# Key_Matrix.net
KiCad netlist of a schematic drawn in Altium Designer
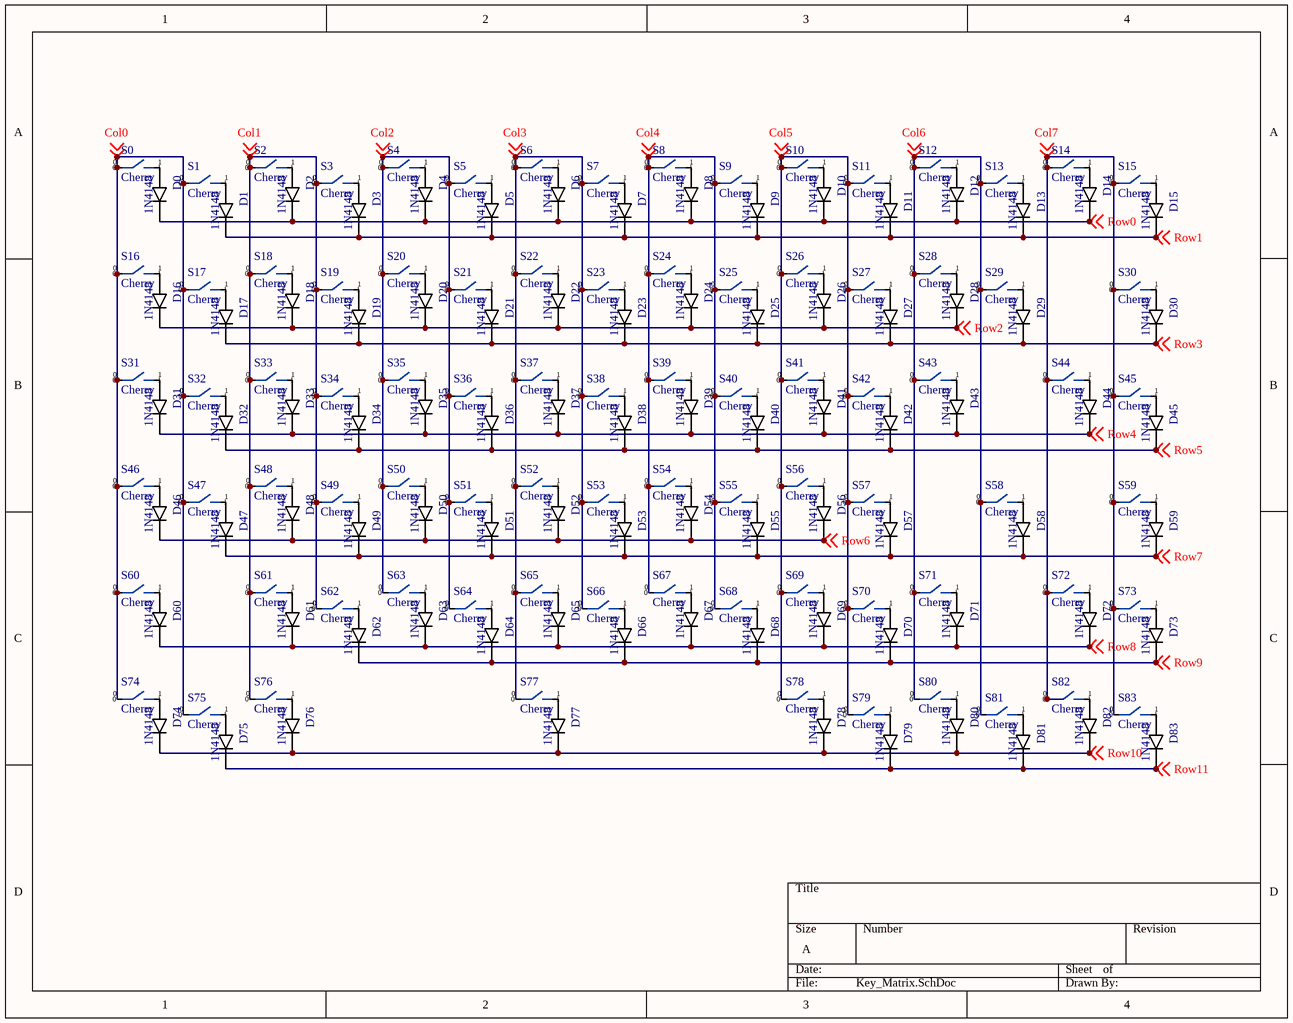
[diagram p0: Key_Matrix.SchDoc]

(export (version "E")
  (design (tool "Eeschema 10.0.6"))
  (components
    (comp (ref "D0")
      (value "1N4148")
      (footprint "DIOAD829W49L456D191_1N4148(Primary)")
      (description "Diode Small Signal Switching 100V 0.3A 2-Pin DO-35")
      (fields (field (name "MF") "MICROSS/On Semiconductor"))
      (libsource (lib "1N4148") (part "1N4148"))
    )
    (comp (ref "D1")
      (value "1N4148")
      (footprint "DIOAD829W49L456D191_1N4148(Primary)")
      (description "Diode Small Signal Switching 100V 0.3A 2-Pin DO-35")
      (fields (field (name "MF") "MICROSS/On Semiconductor"))
      (libsource (lib "1N4148") (part "1N4148"))
    )
    (comp (ref "D2")
      (value "1N4148")
      (footprint "DIOAD829W49L456D191_1N4148(Primary)")
      (description "Diode Small Signal Switching 100V 0.3A 2-Pin DO-35")
      (fields (field (name "MF") "MICROSS/On Semiconductor"))
      (libsource (lib "1N4148") (part "1N4148"))
    )
    (comp (ref "D3")
      (value "1N4148")
      (footprint "DIOAD829W49L456D191_1N4148(Primary)")
      (description "Diode Small Signal Switching 100V 0.3A 2-Pin DO-35")
      (fields (field (name "MF") "MICROSS/On Semiconductor"))
      (libsource (lib "1N4148") (part "1N4148"))
    )
    (comp (ref "D4")
      (value "1N4148")
      (footprint "DIOAD829W49L456D191_1N4148(Primary)")
      (description "Diode Small Signal Switching 100V 0.3A 2-Pin DO-35")
      (fields (field (name "MF") "MICROSS/On Semiconductor"))
      (libsource (lib "1N4148") (part "1N4148"))
    )
    (comp (ref "D5")
      (value "1N4148")
      (footprint "DIOAD829W49L456D191_1N4148(Primary)")
      (description "Diode Small Signal Switching 100V 0.3A 2-Pin DO-35")
      (fields (field (name "MF") "MICROSS/On Semiconductor"))
      (libsource (lib "1N4148") (part "1N4148"))
    )
    (comp (ref "D6")
      (value "1N4148")
      (footprint "DIOAD829W49L456D191_1N4148(Primary)")
      (description "Diode Small Signal Switching 100V 0.3A 2-Pin DO-35")
      (fields (field (name "MF") "MICROSS/On Semiconductor"))
      (libsource (lib "1N4148") (part "1N4148"))
    )
    (comp (ref "D7")
      (value "1N4148")
      (footprint "DIOAD829W49L456D191_1N4148(Primary)")
      (description "Diode Small Signal Switching 100V 0.3A 2-Pin DO-35")
      (fields (field (name "MF") "MICROSS/On Semiconductor"))
      (libsource (lib "1N4148") (part "1N4148"))
    )
    (comp (ref "D8")
      (value "1N4148")
      (footprint "DIOAD829W49L456D191_1N4148(Primary)")
      (description "Diode Small Signal Switching 100V 0.3A 2-Pin DO-35")
      (fields (field (name "MF") "MICROSS/On Semiconductor"))
      (libsource (lib "1N4148") (part "1N4148"))
    )
    (comp (ref "D9")
      (value "1N4148")
      (footprint "DIOAD829W49L456D191_1N4148(Primary)")
      (description "Diode Small Signal Switching 100V 0.3A 2-Pin DO-35")
      (fields (field (name "MF") "MICROSS/On Semiconductor"))
      (libsource (lib "1N4148") (part "1N4148"))
    )
    (comp (ref "D10")
      (value "1N4148")
      (footprint "DIOAD829W49L456D191_1N4148(Primary)")
      (description "Diode Small Signal Switching 100V 0.3A 2-Pin DO-35")
      (fields (field (name "MF") "MICROSS/On Semiconductor"))
      (libsource (lib "1N4148") (part "1N4148"))
    )
    (comp (ref "D11")
      (value "1N4148")
      (footprint "DIOAD829W49L456D191_1N4148(Primary)")
      (description "Diode Small Signal Switching 100V 0.3A 2-Pin DO-35")
      (fields (field (name "MF") "MICROSS/On Semiconductor"))
      (libsource (lib "1N4148") (part "1N4148"))
    )
    (comp (ref "D12")
      (value "1N4148")
      (footprint "DIOAD829W49L456D191_1N4148(Primary)")
      (description "Diode Small Signal Switching 100V 0.3A 2-Pin DO-35")
      (fields (field (name "MF") "MICROSS/On Semiconductor"))
      (libsource (lib "1N4148") (part "1N4148"))
    )
    (comp (ref "D13")
      (value "1N4148")
      (footprint "DIOAD829W49L456D191_1N4148(Primary)")
      (description "Diode Small Signal Switching 100V 0.3A 2-Pin DO-35")
      (fields (field (name "MF") "MICROSS/On Semiconductor"))
      (libsource (lib "1N4148") (part "1N4148"))
    )
    (comp (ref "D14")
      (value "1N4148")
      (footprint "DIOAD829W49L456D191_1N4148(Primary)")
      (description "Diode Small Signal Switching 100V 0.3A 2-Pin DO-35")
      (fields (field (name "MF") "MICROSS/On Semiconductor"))
      (libsource (lib "1N4148") (part "1N4148"))
    )
    (comp (ref "D15")
      (value "1N4148")
      (footprint "DIOAD829W49L456D191_1N4148(Primary)")
      (description "Diode Small Signal Switching 100V 0.3A 2-Pin DO-35")
      (fields (field (name "MF") "MICROSS/On Semiconductor"))
      (libsource (lib "1N4148") (part "1N4148"))
    )
    (comp (ref "D16")
      (value "1N4148")
      (footprint "DIOAD829W49L456D191_1N4148(Primary)")
      (description "Diode Small Signal Switching 100V 0.3A 2-Pin DO-35")
      (fields (field (name "MF") "MICROSS/On Semiconductor"))
      (libsource (lib "1N4148") (part "1N4148"))
    )
    (comp (ref "D17")
      (value "1N4148")
      (footprint "DIOAD829W49L456D191_1N4148(Primary)")
      (description "Diode Small Signal Switching 100V 0.3A 2-Pin DO-35")
      (fields (field (name "MF") "MICROSS/On Semiconductor"))
      (libsource (lib "1N4148") (part "1N4148"))
    )
    (comp (ref "D18")
      (value "1N4148")
      (footprint "DIOAD829W49L456D191_1N4148(Primary)")
      (description "Diode Small Signal Switching 100V 0.3A 2-Pin DO-35")
      (fields (field (name "MF") "MICROSS/On Semiconductor"))
      (libsource (lib "1N4148") (part "1N4148"))
    )
    (comp (ref "D19")
      (value "1N4148")
      (footprint "DIOAD829W49L456D191_1N4148(Primary)")
      (description "Diode Small Signal Switching 100V 0.3A 2-Pin DO-35")
      (fields (field (name "MF") "MICROSS/On Semiconductor"))
      (libsource (lib "1N4148") (part "1N4148"))
    )
    (comp (ref "D20")
      (value "1N4148")
      (footprint "DIOAD829W49L456D191_1N4148(Primary)")
      (description "Diode Small Signal Switching 100V 0.3A 2-Pin DO-35")
      (fields (field (name "MF") "MICROSS/On Semiconductor"))
      (libsource (lib "1N4148") (part "1N4148"))
    )
    (comp (ref "D21")
      (value "1N4148")
      (footprint "DIOAD829W49L456D191_1N4148(Primary)")
      (description "Diode Small Signal Switching 100V 0.3A 2-Pin DO-35")
      (fields (field (name "MF") "MICROSS/On Semiconductor"))
      (libsource (lib "1N4148") (part "1N4148"))
    )
    (comp (ref "D22")
      (value "1N4148")
      (footprint "DIOAD829W49L456D191_1N4148(Primary)")
      (description "Diode Small Signal Switching 100V 0.3A 2-Pin DO-35")
      (fields (field (name "MF") "MICROSS/On Semiconductor"))
      (libsource (lib "1N4148") (part "1N4148"))
    )
    (comp (ref "D23")
      (value "1N4148")
      (footprint "DIOAD829W49L456D191_1N4148(Primary)")
      (description "Diode Small Signal Switching 100V 0.3A 2-Pin DO-35")
      (fields (field (name "MF") "MICROSS/On Semiconductor"))
      (libsource (lib "1N4148") (part "1N4148"))
    )
    (comp (ref "D24")
      (value "1N4148")
      (footprint "DIOAD829W49L456D191_1N4148(Primary)")
      (description "Diode Small Signal Switching 100V 0.3A 2-Pin DO-35")
      (fields (field (name "MF") "MICROSS/On Semiconductor"))
      (libsource (lib "1N4148") (part "1N4148"))
    )
    (comp (ref "D25")
      (value "1N4148")
      (footprint "DIOAD829W49L456D191_1N4148(Primary)")
      (description "Diode Small Signal Switching 100V 0.3A 2-Pin DO-35")
      (fields (field (name "MF") "MICROSS/On Semiconductor"))
      (libsource (lib "1N4148") (part "1N4148"))
    )
    (comp (ref "D26")
      (value "1N4148")
      (footprint "DIOAD829W49L456D191_1N4148(Primary)")
      (description "Diode Small Signal Switching 100V 0.3A 2-Pin DO-35")
      (fields (field (name "MF") "MICROSS/On Semiconductor"))
      (libsource (lib "1N4148") (part "1N4148"))
    )
    (comp (ref "D27")
      (value "1N4148")
      (footprint "DIOAD829W49L456D191_1N4148(Primary)")
      (description "Diode Small Signal Switching 100V 0.3A 2-Pin DO-35")
      (fields (field (name "MF") "MICROSS/On Semiconductor"))
      (libsource (lib "1N4148") (part "1N4148"))
    )
    (comp (ref "D28")
      (value "1N4148")
      (footprint "DIOAD829W49L456D191_1N4148(Primary)")
      (description "Diode Small Signal Switching 100V 0.3A 2-Pin DO-35")
      (fields (field (name "MF") "MICROSS/On Semiconductor"))
      (libsource (lib "1N4148") (part "1N4148"))
    )
    (comp (ref "D29")
      (value "1N4148")
      (footprint "DIOAD829W49L456D191_1N4148(Primary)")
      (description "Diode Small Signal Switching 100V 0.3A 2-Pin DO-35")
      (fields (field (name "MF") "MICROSS/On Semiconductor"))
      (libsource (lib "1N4148") (part "1N4148"))
    )
    (comp (ref "D30")
      (value "1N4148")
      (footprint "DIOAD829W49L456D191_1N4148(Primary)")
      (description "Diode Small Signal Switching 100V 0.3A 2-Pin DO-35")
      (fields (field (name "MF") "MICROSS/On Semiconductor"))
      (libsource (lib "1N4148") (part "1N4148"))
    )
    (comp (ref "D31")
      (value "1N4148")
      (footprint "DIOAD829W49L456D191_1N4148(Primary)")
      (description "Diode Small Signal Switching 100V 0.3A 2-Pin DO-35")
      (fields (field (name "MF") "MICROSS/On Semiconductor"))
      (libsource (lib "1N4148") (part "1N4148"))
    )
    (comp (ref "D32")
      (value "1N4148")
      (footprint "DIOAD829W49L456D191_1N4148(Primary)")
      (description "Diode Small Signal Switching 100V 0.3A 2-Pin DO-35")
      (fields (field (name "MF") "MICROSS/On Semiconductor"))
      (libsource (lib "1N4148") (part "1N4148"))
    )
    (comp (ref "D33")
      (value "1N4148")
      (footprint "DIOAD829W49L456D191_1N4148(Primary)")
      (description "Diode Small Signal Switching 100V 0.3A 2-Pin DO-35")
      (fields (field (name "MF") "MICROSS/On Semiconductor"))
      (libsource (lib "1N4148") (part "1N4148"))
    )
    (comp (ref "D34")
      (value "1N4148")
      (footprint "DIOAD829W49L456D191_1N4148(Primary)")
      (description "Diode Small Signal Switching 100V 0.3A 2-Pin DO-35")
      (fields (field (name "MF") "MICROSS/On Semiconductor"))
      (libsource (lib "1N4148") (part "1N4148"))
    )
    (comp (ref "D35")
      (value "1N4148")
      (footprint "DIOAD829W49L456D191_1N4148(Primary)")
      (description "Diode Small Signal Switching 100V 0.3A 2-Pin DO-35")
      (fields (field (name "MF") "MICROSS/On Semiconductor"))
      (libsource (lib "1N4148") (part "1N4148"))
    )
    (comp (ref "D36")
      (value "1N4148")
      (footprint "DIOAD829W49L456D191_1N4148(Primary)")
      (description "Diode Small Signal Switching 100V 0.3A 2-Pin DO-35")
      (fields (field (name "MF") "MICROSS/On Semiconductor"))
      (libsource (lib "1N4148") (part "1N4148"))
    )
    (comp (ref "D37")
      (value "1N4148")
      (footprint "DIOAD829W49L456D191_1N4148(Primary)")
      (description "Diode Small Signal Switching 100V 0.3A 2-Pin DO-35")
      (fields (field (name "MF") "MICROSS/On Semiconductor"))
      (libsource (lib "1N4148") (part "1N4148"))
    )
    (comp (ref "D38")
      (value "1N4148")
      (footprint "DIOAD829W49L456D191_1N4148(Primary)")
      (description "Diode Small Signal Switching 100V 0.3A 2-Pin DO-35")
      (fields (field (name "MF") "MICROSS/On Semiconductor"))
      (libsource (lib "1N4148") (part "1N4148"))
    )
    (comp (ref "D39")
      (value "1N4148")
      (footprint "DIOAD829W49L456D191_1N4148(Primary)")
      (description "Diode Small Signal Switching 100V 0.3A 2-Pin DO-35")
      (fields (field (name "MF") "MICROSS/On Semiconductor"))
      (libsource (lib "1N4148") (part "1N4148"))
    )
    (comp (ref "D40")
      (value "1N4148")
      (footprint "DIOAD829W49L456D191_1N4148(Primary)")
      (description "Diode Small Signal Switching 100V 0.3A 2-Pin DO-35")
      (fields (field (name "MF") "MICROSS/On Semiconductor"))
      (libsource (lib "1N4148") (part "1N4148"))
    )
    (comp (ref "D41")
      (value "1N4148")
      (footprint "DIOAD829W49L456D191_1N4148(Primary)")
      (description "Diode Small Signal Switching 100V 0.3A 2-Pin DO-35")
      (fields (field (name "MF") "MICROSS/On Semiconductor"))
      (libsource (lib "1N4148") (part "1N4148"))
    )
    (comp (ref "D42")
      (value "1N4148")
      (footprint "DIOAD829W49L456D191_1N4148(Primary)")
      (description "Diode Small Signal Switching 100V 0.3A 2-Pin DO-35")
      (fields (field (name "MF") "MICROSS/On Semiconductor"))
      (libsource (lib "1N4148") (part "1N4148"))
    )
    (comp (ref "D43")
      (value "1N4148")
      (footprint "DIOAD829W49L456D191_1N4148(Primary)")
      (description "Diode Small Signal Switching 100V 0.3A 2-Pin DO-35")
      (fields (field (name "MF") "MICROSS/On Semiconductor"))
      (libsource (lib "1N4148") (part "1N4148"))
    )
    (comp (ref "D44")
      (value "1N4148")
      (footprint "DIOAD829W49L456D191_1N4148(Primary)")
      (description "Diode Small Signal Switching 100V 0.3A 2-Pin DO-35")
      (fields (field (name "MF") "MICROSS/On Semiconductor"))
      (libsource (lib "1N4148") (part "1N4148"))
    )
    (comp (ref "D45")
      (value "1N4148")
      (footprint "DIOAD829W49L456D191_1N4148(Primary)")
      (description "Diode Small Signal Switching 100V 0.3A 2-Pin DO-35")
      (fields (field (name "MF") "MICROSS/On Semiconductor"))
      (libsource (lib "1N4148") (part "1N4148"))
    )
    (comp (ref "D46")
      (value "1N4148")
      (footprint "DIOAD829W49L456D191_1N4148(Primary)")
      (description "Diode Small Signal Switching 100V 0.3A 2-Pin DO-35")
      (fields (field (name "MF") "MICROSS/On Semiconductor"))
      (libsource (lib "1N4148") (part "1N4148"))
    )
    (comp (ref "D47")
      (value "1N4148")
      (footprint "DIOAD829W49L456D191_1N4148(Primary)")
      (description "Diode Small Signal Switching 100V 0.3A 2-Pin DO-35")
      (fields (field (name "MF") "MICROSS/On Semiconductor"))
      (libsource (lib "1N4148") (part "1N4148"))
    )
    (comp (ref "D48")
      (value "1N4148")
      (footprint "DIOAD829W49L456D191_1N4148(Primary)")
      (description "Diode Small Signal Switching 100V 0.3A 2-Pin DO-35")
      (fields (field (name "MF") "MICROSS/On Semiconductor"))
      (libsource (lib "1N4148") (part "1N4148"))
    )
    (comp (ref "D49")
      (value "1N4148")
      (footprint "DIOAD829W49L456D191_1N4148(Primary)")
      (description "Diode Small Signal Switching 100V 0.3A 2-Pin DO-35")
      (fields (field (name "MF") "MICROSS/On Semiconductor"))
      (libsource (lib "1N4148") (part "1N4148"))
    )
    (comp (ref "D50")
      (value "1N4148")
      (footprint "DIOAD829W49L456D191_1N4148(Primary)")
      (description "Diode Small Signal Switching 100V 0.3A 2-Pin DO-35")
      (fields (field (name "MF") "MICROSS/On Semiconductor"))
      (libsource (lib "1N4148") (part "1N4148"))
    )
    (comp (ref "D51")
      (value "1N4148")
      (footprint "DIOAD829W49L456D191_1N4148(Primary)")
      (description "Diode Small Signal Switching 100V 0.3A 2-Pin DO-35")
      (fields (field (name "MF") "MICROSS/On Semiconductor"))
      (libsource (lib "1N4148") (part "1N4148"))
    )
    (comp (ref "D52")
      (value "1N4148")
      (footprint "DIOAD829W49L456D191_1N4148(Primary)")
      (description "Diode Small Signal Switching 100V 0.3A 2-Pin DO-35")
      (fields (field (name "MF") "MICROSS/On Semiconductor"))
      (libsource (lib "1N4148") (part "1N4148"))
    )
    (comp (ref "D53")
      (value "1N4148")
      (footprint "DIOAD829W49L456D191_1N4148(Primary)")
      (description "Diode Small Signal Switching 100V 0.3A 2-Pin DO-35")
      (fields (field (name "MF") "MICROSS/On Semiconductor"))
      (libsource (lib "1N4148") (part "1N4148"))
    )
    (comp (ref "D54")
      (value "1N4148")
      (footprint "DIOAD829W49L456D191_1N4148(Primary)")
      (description "Diode Small Signal Switching 100V 0.3A 2-Pin DO-35")
      (fields (field (name "MF") "MICROSS/On Semiconductor"))
      (libsource (lib "1N4148") (part "1N4148"))
    )
    (comp (ref "D55")
      (value "1N4148")
      (footprint "DIOAD829W49L456D191_1N4148(Primary)")
      (description "Diode Small Signal Switching 100V 0.3A 2-Pin DO-35")
      (fields (field (name "MF") "MICROSS/On Semiconductor"))
      (libsource (lib "1N4148") (part "1N4148"))
    )
    (comp (ref "D56")
      (value "1N4148")
      (footprint "DIOAD829W49L456D191_1N4148(Primary)")
      (description "Diode Small Signal Switching 100V 0.3A 2-Pin DO-35")
      (fields (field (name "MF") "MICROSS/On Semiconductor"))
      (libsource (lib "1N4148") (part "1N4148"))
    )
    (comp (ref "D57")
      (value "1N4148")
      (footprint "DIOAD829W49L456D191_1N4148(Primary)")
      (description "Diode Small Signal Switching 100V 0.3A 2-Pin DO-35")
      (fields (field (name "MF") "MICROSS/On Semiconductor"))
      (libsource (lib "1N4148") (part "1N4148"))
    )
    (comp (ref "D58")
      (value "1N4148")
      (footprint "DIOAD829W49L456D191_1N4148(Primary)")
      (description "Diode Small Signal Switching 100V 0.3A 2-Pin DO-35")
      (fields (field (name "MF") "MICROSS/On Semiconductor"))
      (libsource (lib "1N4148") (part "1N4148"))
    )
    (comp (ref "D59")
      (value "1N4148")
      (footprint "DIOAD829W49L456D191_1N4148(Primary)")
      (description "Diode Small Signal Switching 100V 0.3A 2-Pin DO-35")
      (fields (field (name "MF") "MICROSS/On Semiconductor"))
      (libsource (lib "1N4148") (part "1N4148"))
    )
    (comp (ref "D60")
      (value "1N4148")
      (footprint "DIOAD829W49L456D191_1N4148(Primary)")
      (description "Diode Small Signal Switching 100V 0.3A 2-Pin DO-35")
      (fields (field (name "MF") "MICROSS/On Semiconductor"))
      (libsource (lib "1N4148") (part "1N4148"))
    )
    (comp (ref "D61")
      (value "1N4148")
      (footprint "DIOAD829W49L456D191_1N4148(Primary)")
      (description "Diode Small Signal Switching 100V 0.3A 2-Pin DO-35")
      (fields (field (name "MF") "MICROSS/On Semiconductor"))
      (libsource (lib "1N4148") (part "1N4148"))
    )
    (comp (ref "D62")
      (value "1N4148")
      (footprint "DIOAD829W49L456D191_1N4148(Primary)")
      (description "Diode Small Signal Switching 100V 0.3A 2-Pin DO-35")
      (fields (field (name "MF") "MICROSS/On Semiconductor"))
      (libsource (lib "1N4148") (part "1N4148"))
    )
    (comp (ref "D63")
      (value "1N4148")
      (footprint "DIOAD829W49L456D191_1N4148(Primary)")
      (description "Diode Small Signal Switching 100V 0.3A 2-Pin DO-35")
      (fields (field (name "MF") "MICROSS/On Semiconductor"))
      (libsource (lib "1N4148") (part "1N4148"))
    )
    (comp (ref "D64")
      (value "1N4148")
      (footprint "DIOAD829W49L456D191_1N4148(Primary)")
      (description "Diode Small Signal Switching 100V 0.3A 2-Pin DO-35")
      (fields (field (name "MF") "MICROSS/On Semiconductor"))
      (libsource (lib "1N4148") (part "1N4148"))
    )
    (comp (ref "D65")
      (value "1N4148")
      (footprint "DIOAD829W49L456D191_1N4148(Primary)")
      (description "Diode Small Signal Switching 100V 0.3A 2-Pin DO-35")
      (fields (field (name "MF") "MICROSS/On Semiconductor"))
      (libsource (lib "1N4148") (part "1N4148"))
    )
    (comp (ref "D66")
      (value "1N4148")
      (footprint "DIOAD829W49L456D191_1N4148(Primary)")
      (description "Diode Small Signal Switching 100V 0.3A 2-Pin DO-35")
      (fields (field (name "MF") "MICROSS/On Semiconductor"))
      (libsource (lib "1N4148") (part "1N4148"))
    )
    (comp (ref "D67")
      (value "1N4148")
      (footprint "DIOAD829W49L456D191_1N4148(Primary)")
      (description "Diode Small Signal Switching 100V 0.3A 2-Pin DO-35")
      (fields (field (name "MF") "MICROSS/On Semiconductor"))
      (libsource (lib "1N4148") (part "1N4148"))
    )
    (comp (ref "D68")
      (value "1N4148")
      (footprint "DIOAD829W49L456D191_1N4148(Primary)")
      (description "Diode Small Signal Switching 100V 0.3A 2-Pin DO-35")
      (fields (field (name "MF") "MICROSS/On Semiconductor"))
      (libsource (lib "1N4148") (part "1N4148"))
    )
    (comp (ref "D69")
      (value "1N4148")
      (footprint "DIOAD829W49L456D191_1N4148(Primary)")
      (description "Diode Small Signal Switching 100V 0.3A 2-Pin DO-35")
      (fields (field (name "MF") "MICROSS/On Semiconductor"))
      (libsource (lib "1N4148") (part "1N4148"))
    )
    (comp (ref "D70")
      (value "1N4148")
      (footprint "DIOAD829W49L456D191_1N4148(Primary)")
      (description "Diode Small Signal Switching 100V 0.3A 2-Pin DO-35")
      (fields (field (name "MF") "MICROSS/On Semiconductor"))
      (libsource (lib "1N4148") (part "1N4148"))
    )
    (comp (ref "D71")
      (value "1N4148")
      (footprint "DIOAD829W49L456D191_1N4148(Primary)")
      (description "Diode Small Signal Switching 100V 0.3A 2-Pin DO-35")
      (fields (field (name "MF") "MICROSS/On Semiconductor"))
      (libsource (lib "1N4148") (part "1N4148"))
    )
    (comp (ref "D72")
      (value "1N4148")
      (footprint "DIOAD829W49L456D191_1N4148(Primary)")
      (description "Diode Small Signal Switching 100V 0.3A 2-Pin DO-35")
      (fields (field (name "MF") "MICROSS/On Semiconductor"))
      (libsource (lib "1N4148") (part "1N4148"))
    )
    (comp (ref "D73")
      (value "1N4148")
      (footprint "DIOAD829W49L456D191_1N4148(Primary)")
      (description "Diode Small Signal Switching 100V 0.3A 2-Pin DO-35")
      (fields (field (name "MF") "MICROSS/On Semiconductor"))
      (libsource (lib "1N4148") (part "1N4148"))
    )
    (comp (ref "D74")
      (value "1N4148")
      (footprint "DIOAD829W49L456D191_1N4148(Primary)")
      (description "Diode Small Signal Switching 100V 0.3A 2-Pin DO-35")
      (fields (field (name "MF") "MICROSS/On Semiconductor"))
      (libsource (lib "1N4148") (part "1N4148"))
    )
    (comp (ref "D75")
      (value "1N4148")
      (footprint "DIOAD829W49L456D191_1N4148(Primary)")
      (description "Diode Small Signal Switching 100V 0.3A 2-Pin DO-35")
      (fields (field (name "MF") "MICROSS/On Semiconductor"))
      (libsource (lib "1N4148") (part "1N4148"))
    )
    (comp (ref "D76")
      (value "1N4148")
      (footprint "DIOAD829W49L456D191_1N4148(Primary)")
      (description "Diode Small Signal Switching 100V 0.3A 2-Pin DO-35")
      (fields (field (name "MF") "MICROSS/On Semiconductor"))
      (libsource (lib "1N4148") (part "1N4148"))
    )
    (comp (ref "D77")
      (value "1N4148")
      (footprint "DIOAD829W49L456D191_1N4148(Primary)")
      (description "Diode Small Signal Switching 100V 0.3A 2-Pin DO-35")
      (fields (field (name "MF") "MICROSS/On Semiconductor"))
      (libsource (lib "1N4148") (part "1N4148"))
    )
    (comp (ref "D78")
      (value "1N4148")
      (footprint "DIOAD829W49L456D191_1N4148(Primary)")
      (description "Diode Small Signal Switching 100V 0.3A 2-Pin DO-35")
      (fields (field (name "MF") "MICROSS/On Semiconductor"))
      (libsource (lib "1N4148") (part "1N4148"))
    )
    (comp (ref "D79")
      (value "1N4148")
      (footprint "DIOAD829W49L456D191_1N4148(Primary)")
      (description "Diode Small Signal Switching 100V 0.3A 2-Pin DO-35")
      (fields (field (name "MF") "MICROSS/On Semiconductor"))
      (libsource (lib "1N4148") (part "1N4148"))
    )
    (comp (ref "D80")
      (value "1N4148")
      (footprint "DIOAD829W49L456D191_1N4148(Primary)")
      (description "Diode Small Signal Switching 100V 0.3A 2-Pin DO-35")
      (fields (field (name "MF") "MICROSS/On Semiconductor"))
      (libsource (lib "1N4148") (part "1N4148"))
    )
    (comp (ref "D81")
      (value "1N4148")
      (footprint "DIOAD829W49L456D191_1N4148(Primary)")
      (description "Diode Small Signal Switching 100V 0.3A 2-Pin DO-35")
      (fields (field (name "MF") "MICROSS/On Semiconductor"))
      (libsource (lib "1N4148") (part "1N4148"))
    )
    (comp (ref "D82")
      (value "1N4148")
      (footprint "DIOAD829W49L456D191_1N4148(Primary)")
      (description "Diode Small Signal Switching 100V 0.3A 2-Pin DO-35")
      (fields (field (name "MF") "MICROSS/On Semiconductor"))
      (libsource (lib "1N4148") (part "1N4148"))
    )
    (comp (ref "D83")
      (value "1N4148")
      (footprint "DIOAD829W49L456D191_1N4148(Primary)")
      (description "Diode Small Signal Switching 100V 0.3A 2-Pin DO-35")
      (fields (field (name "MF") "MICROSS/On Semiconductor"))
      (libsource (lib "1N4148") (part "1N4148"))
    )
    (comp (ref "S0")
      (value "Cherry")
      (footprint "CHERRY-MX-LED-1U")
      (description "Cherry SPST Keyswitch")
      (libsource (lib "CherryMX_Footprints") (part "Cherry_Switch"))
    )
    (comp (ref "S1")
      (value "Cherry")
      (footprint "CHERRY-MX-LED-1U")
      (description "Cherry SPST Keyswitch")
      (libsource (lib "CherryMX_Footprints") (part "Cherry_Switch"))
    )
    (comp (ref "S2")
      (value "Cherry")
      (footprint "CHERRY-MX-LED-1U")
      (description "Cherry SPST Keyswitch")
      (libsource (lib "CherryMX_Footprints") (part "Cherry_Switch"))
    )
    (comp (ref "S3")
      (value "Cherry")
      (footprint "CHERRY-MX-LED-1U")
      (description "Cherry SPST Keyswitch")
      (libsource (lib "CherryMX_Footprints") (part "Cherry_Switch"))
    )
    (comp (ref "S4")
      (value "Cherry")
      (footprint "CHERRY-MX-LED-1U")
      (description "Cherry SPST Keyswitch")
      (libsource (lib "CherryMX_Footprints") (part "Cherry_Switch"))
    )
    (comp (ref "S5")
      (value "Cherry")
      (footprint "CHERRY-MX-LED-1U")
      (description "Cherry SPST Keyswitch")
      (libsource (lib "CherryMX_Footprints") (part "Cherry_Switch"))
    )
    (comp (ref "S6")
      (value "Cherry")
      (footprint "CHERRY-MX-LED-1U")
      (description "Cherry SPST Keyswitch")
      (libsource (lib "CherryMX_Footprints") (part "Cherry_Switch"))
    )
    (comp (ref "S7")
      (value "Cherry")
      (footprint "CHERRY-MX-LED-1U")
      (description "Cherry SPST Keyswitch")
      (libsource (lib "CherryMX_Footprints") (part "Cherry_Switch"))
    )
    (comp (ref "S8")
      (value "Cherry")
      (footprint "CHERRY-MX-LED-1U")
      (description "Cherry SPST Keyswitch")
      (libsource (lib "CherryMX_Footprints") (part "Cherry_Switch"))
    )
    (comp (ref "S9")
      (value "Cherry")
      (footprint "CHERRY-MX-LED-1U")
      (description "Cherry SPST Keyswitch")
      (libsource (lib "CherryMX_Footprints") (part "Cherry_Switch"))
    )
    (comp (ref "S10")
      (value "Cherry")
      (footprint "CHERRY-MX-LED-1U")
      (description "Cherry SPST Keyswitch")
      (libsource (lib "CherryMX_Footprints") (part "Cherry_Switch"))
    )
    (comp (ref "S11")
      (value "Cherry")
      (footprint "CHERRY-MX-LED-1U")
      (description "Cherry SPST Keyswitch")
      (libsource (lib "CherryMX_Footprints") (part "Cherry_Switch"))
    )
    (comp (ref "S12")
      (value "Cherry")
      (footprint "CHERRY-MX-LED-1U")
      (description "Cherry SPST Keyswitch")
      (libsource (lib "CherryMX_Footprints") (part "Cherry_Switch"))
    )
    (comp (ref "S13")
      (value "Cherry")
      (footprint "CHERRY-MX-LED-1U")
      (description "Cherry SPST Keyswitch")
      (libsource (lib "CherryMX_Footprints") (part "Cherry_Switch"))
    )
    (comp (ref "S14")
      (value "Cherry")
      (footprint "CHERRY-MX-LED-1U")
      (description "Cherry SPST Keyswitch")
      (libsource (lib "CherryMX_Footprints") (part "Cherry_Switch"))
    )
    (comp (ref "S15")
      (value "Cherry")
      (footprint "CHERRY-MX-LED-1U")
      (description "Cherry SPST Keyswitch")
      (libsource (lib "CherryMX_Footprints") (part "Cherry_Switch"))
    )
    (comp (ref "S16")
      (value "Cherry")
      (footprint "CHERRY-MX-LED-1U")
      (description "Cherry SPST Keyswitch")
      (libsource (lib "CherryMX_Footprints") (part "Cherry_Switch"))
    )
    (comp (ref "S17")
      (value "Cherry")
      (footprint "CHERRY-MX-LED-1U")
      (description "Cherry SPST Keyswitch")
      (libsource (lib "CherryMX_Footprints") (part "Cherry_Switch"))
    )
    (comp (ref "S18")
      (value "Cherry")
      (footprint "CHERRY-MX-LED-1U")
      (description "Cherry SPST Keyswitch")
      (libsource (lib "CherryMX_Footprints") (part "Cherry_Switch"))
    )
    (comp (ref "S19")
      (value "Cherry")
      (footprint "CHERRY-MX-LED-1U")
      (description "Cherry SPST Keyswitch")
      (libsource (lib "CherryMX_Footprints") (part "Cherry_Switch"))
    )
    (comp (ref "S20")
      (value "Cherry")
      (footprint "CHERRY-MX-LED-1U")
      (description "Cherry SPST Keyswitch")
      (libsource (lib "CherryMX_Footprints") (part "Cherry_Switch"))
    )
    (comp (ref "S21")
      (value "Cherry")
      (footprint "CHERRY-MX-LED-1U")
      (description "Cherry SPST Keyswitch")
      (libsource (lib "CherryMX_Footprints") (part "Cherry_Switch"))
    )
    (comp (ref "S22")
      (value "Cherry")
      (footprint "CHERRY-MX-LED-1U")
      (description "Cherry SPST Keyswitch")
      (libsource (lib "CherryMX_Footprints") (part "Cherry_Switch"))
    )
    (comp (ref "S23")
      (value "Cherry")
      (footprint "CHERRY-MX-LED-1U")
      (description "Cherry SPST Keyswitch")
      (libsource (lib "CherryMX_Footprints") (part "Cherry_Switch"))
    )
    (comp (ref "S24")
      (value "Cherry")
      (footprint "CHERRY-MX-LED-1U")
      (description "Cherry SPST Keyswitch")
      (libsource (lib "CherryMX_Footprints") (part "Cherry_Switch"))
    )
    (comp (ref "S25")
      (value "Cherry")
      (footprint "CHERRY-MX-LED-1U")
      (description "Cherry SPST Keyswitch")
      (libsource (lib "CherryMX_Footprints") (part "Cherry_Switch"))
    )
    (comp (ref "S26")
      (value "Cherry")
      (footprint "CHERRY-MX-LED-1U")
      (description "Cherry SPST Keyswitch")
      (libsource (lib "CherryMX_Footprints") (part "Cherry_Switch"))
    )
    (comp (ref "S27")
      (value "Cherry")
      (footprint "CHERRY-MX-LED-1U")
      (description "Cherry SPST Keyswitch")
      (libsource (lib "CherryMX_Footprints") (part "Cherry_Switch"))
    )
    (comp (ref "S28")
      (value "Cherry")
      (footprint "CHERRY-MX-LED-1U")
      (description "Cherry SPST Keyswitch")
      (libsource (lib "CherryMX_Footprints") (part "Cherry_Switch"))
    )
    (comp (ref "S29")
      (value "Cherry")
      (footprint "CHERRY-MX-LED-1U")
      (description "Cherry SPST Keyswitch")
      (libsource (lib "CherryMX_Footprints") (part "Cherry_Switch"))
    )
    (comp (ref "S30")
      (value "Cherry")
      (footprint "CHERRY-MX-LED-1U")
      (description "Cherry SPST Keyswitch")
      (libsource (lib "CherryMX_Footprints") (part "Cherry_Switch"))
    )
    (comp (ref "S31")
      (value "Cherry")
      (footprint "CHERRY-MX-LED-1U")
      (description "Cherry SPST Keyswitch")
      (libsource (lib "CherryMX_Footprints") (part "Cherry_Switch"))
    )
    (comp (ref "S32")
      (value "Cherry")
      (footprint "CHERRY-MX-LED-1U")
      (description "Cherry SPST Keyswitch")
      (libsource (lib "CherryMX_Footprints") (part "Cherry_Switch"))
    )
    (comp (ref "S33")
      (value "Cherry")
      (footprint "CHERRY-MX-LED-1U")
      (description "Cherry SPST Keyswitch")
      (libsource (lib "CherryMX_Footprints") (part "Cherry_Switch"))
    )
    (comp (ref "S34")
      (value "Cherry")
      (footprint "CHERRY-MX-LED-1U")
      (description "Cherry SPST Keyswitch")
      (libsource (lib "CherryMX_Footprints") (part "Cherry_Switch"))
    )
    (comp (ref "S35")
      (value "Cherry")
      (footprint "CHERRY-MX-LED-1U")
      (description "Cherry SPST Keyswitch")
      (libsource (lib "CherryMX_Footprints") (part "Cherry_Switch"))
    )
    (comp (ref "S36")
      (value "Cherry")
      (footprint "CHERRY-MX-LED-1U")
      (description "Cherry SPST Keyswitch")
      (libsource (lib "CherryMX_Footprints") (part "Cherry_Switch"))
    )
    (comp (ref "S37")
      (value "Cherry")
      (footprint "CHERRY-MX-LED-1U")
      (description "Cherry SPST Keyswitch")
      (libsource (lib "CherryMX_Footprints") (part "Cherry_Switch"))
    )
    (comp (ref "S38")
      (value "Cherry")
      (footprint "CHERRY-MX-LED-1U")
      (description "Cherry SPST Keyswitch")
      (libsource (lib "CherryMX_Footprints") (part "Cherry_Switch"))
    )
    (comp (ref "S39")
      (value "Cherry")
      (footprint "CHERRY-MX-LED-1U")
      (description "Cherry SPST Keyswitch")
      (libsource (lib "CherryMX_Footprints") (part "Cherry_Switch"))
    )
    (comp (ref "S40")
      (value "Cherry")
      (footprint "CHERRY-MX-LED-1U")
      (description "Cherry SPST Keyswitch")
      (libsource (lib "CherryMX_Footprints") (part "Cherry_Switch"))
    )
    (comp (ref "S41")
      (value "Cherry")
      (footprint "CHERRY-MX-LED-1U")
      (description "Cherry SPST Keyswitch")
      (libsource (lib "CherryMX_Footprints") (part "Cherry_Switch"))
    )
    (comp (ref "S42")
      (value "Cherry")
      (footprint "CHERRY-MX-LED-1U")
      (description "Cherry SPST Keyswitch")
      (libsource (lib "CherryMX_Footprints") (part "Cherry_Switch"))
    )
    (comp (ref "S43")
      (value "Cherry")
      (footprint "CHERRY-MX-LED-1U")
      (description "Cherry SPST Keyswitch")
      (libsource (lib "CherryMX_Footprints") (part "Cherry_Switch"))
    )
    (comp (ref "S44")
      (value "Cherry")
      (footprint "CHERRY-MX-LED-1U")
      (description "Cherry SPST Keyswitch")
      (libsource (lib "CherryMX_Footprints") (part "Cherry_Switch"))
    )
    (comp (ref "S45")
      (value "Cherry")
      (footprint "CHERRY-MX-LED-1U")
      (description "Cherry SPST Keyswitch")
      (libsource (lib "CherryMX_Footprints") (part "Cherry_Switch"))
    )
    (comp (ref "S46")
      (value "Cherry")
      (footprint "CHERRY-MX-LED-1U")
      (description "Cherry SPST Keyswitch")
      (libsource (lib "CherryMX_Footprints") (part "Cherry_Switch"))
    )
    (comp (ref "S47")
      (value "Cherry")
      (footprint "CHERRY-MX-LED-1U")
      (description "Cherry SPST Keyswitch")
      (libsource (lib "CherryMX_Footprints") (part "Cherry_Switch"))
    )
    (comp (ref "S48")
      (value "Cherry")
      (footprint "CHERRY-MX-LED-1U")
      (description "Cherry SPST Keyswitch")
      (libsource (lib "CherryMX_Footprints") (part "Cherry_Switch"))
    )
    (comp (ref "S49")
      (value "Cherry")
      (footprint "CHERRY-MX-LED-1U")
      (description "Cherry SPST Keyswitch")
      (libsource (lib "CherryMX_Footprints") (part "Cherry_Switch"))
    )
    (comp (ref "S50")
      (value "Cherry")
      (footprint "CHERRY-MX-LED-1U")
      (description "Cherry SPST Keyswitch")
      (libsource (lib "CherryMX_Footprints") (part "Cherry_Switch"))
    )
    (comp (ref "S51")
      (value "Cherry")
      (footprint "CHERRY-MX-LED-1U")
      (description "Cherry SPST Keyswitch")
      (libsource (lib "CherryMX_Footprints") (part "Cherry_Switch"))
    )
    (comp (ref "S52")
      (value "Cherry")
      (footprint "CHERRY-MX-LED-1U")
      (description "Cherry SPST Keyswitch")
      (libsource (lib "CherryMX_Footprints") (part "Cherry_Switch"))
    )
    (comp (ref "S53")
      (value "Cherry")
      (footprint "CHERRY-MX-LED-1U")
      (description "Cherry SPST Keyswitch")
      (libsource (lib "CherryMX_Footprints") (part "Cherry_Switch"))
    )
    (comp (ref "S54")
      (value "Cherry")
      (footprint "CHERRY-MX-LED-1U")
      (description "Cherry SPST Keyswitch")
      (libsource (lib "CherryMX_Footprints") (part "Cherry_Switch"))
    )
    (comp (ref "S55")
      (value "Cherry")
      (footprint "CHERRY-MX-LED-1U")
      (description "Cherry SPST Keyswitch")
      (libsource (lib "CherryMX_Footprints") (part "Cherry_Switch"))
    )
    (comp (ref "S56")
      (value "Cherry")
      (footprint "CHERRY-MX-LED-1U")
      (description "Cherry SPST Keyswitch")
      (libsource (lib "CherryMX_Footprints") (part "Cherry_Switch"))
    )
    (comp (ref "S57")
      (value "Cherry")
      (footprint "CHERRY-MX-LED-1U")
      (description "Cherry SPST Keyswitch")
      (libsource (lib "CherryMX_Footprints") (part "Cherry_Switch"))
    )
    (comp (ref "S58")
      (value "Cherry")
      (footprint "CHERRY-MX-LED-1U")
      (description "Cherry SPST Keyswitch")
      (libsource (lib "CherryMX_Footprints") (part "Cherry_Switch"))
    )
    (comp (ref "S59")
      (value "Cherry")
      (footprint "CHERRY-MX-LED-1U")
      (description "Cherry SPST Keyswitch")
      (libsource (lib "CherryMX_Footprints") (part "Cherry_Switch"))
    )
    (comp (ref "S60")
      (value "Cherry")
      (footprint "CHERRY-MX-LED-1U")
      (description "Cherry SPST Keyswitch")
      (libsource (lib "CherryMX_Footprints") (part "Cherry_Switch"))
    )
    (comp (ref "S61")
      (value "Cherry")
      (footprint "CHERRY-MX-LED-1U")
      (description "Cherry SPST Keyswitch")
      (libsource (lib "CherryMX_Footprints") (part "Cherry_Switch"))
    )
    (comp (ref "S62")
      (value "Cherry")
      (footprint "CHERRY-MX-LED-1U")
      (description "Cherry SPST Keyswitch")
      (libsource (lib "CherryMX_Footprints") (part "Cherry_Switch"))
    )
    (comp (ref "S63")
      (value "Cherry")
      (footprint "CHERRY-MX-LED-1U")
      (description "Cherry SPST Keyswitch")
      (libsource (lib "CherryMX_Footprints") (part "Cherry_Switch"))
    )
    (comp (ref "S64")
      (value "Cherry")
      (footprint "CHERRY-MX-LED-1U")
      (description "Cherry SPST Keyswitch")
      (libsource (lib "CherryMX_Footprints") (part "Cherry_Switch"))
    )
    (comp (ref "S65")
      (value "Cherry")
      (footprint "CHERRY-MX-LED-1U")
      (description "Cherry SPST Keyswitch")
      (libsource (lib "CherryMX_Footprints") (part "Cherry_Switch"))
    )
    (comp (ref "S66")
      (value "Cherry")
      (footprint "CHERRY-MX-LED-1U")
      (description "Cherry SPST Keyswitch")
      (libsource (lib "CherryMX_Footprints") (part "Cherry_Switch"))
    )
    (comp (ref "S67")
      (value "Cherry")
      (footprint "CHERRY-MX-LED-1U")
      (description "Cherry SPST Keyswitch")
      (libsource (lib "CherryMX_Footprints") (part "Cherry_Switch"))
    )
    (comp (ref "S68")
      (value "Cherry")
      (footprint "CHERRY-MX-LED-1U")
      (description "Cherry SPST Keyswitch")
      (libsource (lib "CherryMX_Footprints") (part "Cherry_Switch"))
    )
    (comp (ref "S69")
      (value "Cherry")
      (footprint "CHERRY-MX-LED-1U")
      (description "Cherry SPST Keyswitch")
      (libsource (lib "CherryMX_Footprints") (part "Cherry_Switch"))
    )
    (comp (ref "S70")
      (value "Cherry")
      (footprint "CHERRY-MX-LED-1U")
      (description "Cherry SPST Keyswitch")
      (libsource (lib "CherryMX_Footprints") (part "Cherry_Switch"))
    )
    (comp (ref "S71")
      (value "Cherry")
      (footprint "CHERRY-MX-LED-1U")
      (description "Cherry SPST Keyswitch")
      (libsource (lib "CherryMX_Footprints") (part "Cherry_Switch"))
    )
    (comp (ref "S72")
      (value "Cherry")
      (footprint "CHERRY-MX-LED-1U")
      (description "Cherry SPST Keyswitch")
      (libsource (lib "CherryMX_Footprints") (part "Cherry_Switch"))
    )
    (comp (ref "S73")
      (value "Cherry")
      (footprint "CHERRY-MX-LED-1U")
      (description "Cherry SPST Keyswitch")
      (libsource (lib "CherryMX_Footprints") (part "Cherry_Switch"))
    )
    (comp (ref "S74")
      (value "Cherry")
      (footprint "CHERRY-MX-LED-1U")
      (description "Cherry SPST Keyswitch")
      (libsource (lib "CherryMX_Footprints") (part "Cherry_Switch"))
    )
    (comp (ref "S75")
      (value "Cherry")
      (footprint "CHERRY-MX-LED-1U")
      (description "Cherry SPST Keyswitch")
      (libsource (lib "CherryMX_Footprints") (part "Cherry_Switch"))
    )
    (comp (ref "S76")
      (value "Cherry")
      (footprint "CHERRY-MX-LED-1U")
      (description "Cherry SPST Keyswitch")
      (libsource (lib "CherryMX_Footprints") (part "Cherry_Switch"))
    )
    (comp (ref "S77")
      (value "Cherry")
      (footprint "CHERRY-MX-LED-1U")
      (description "Cherry SPST Keyswitch")
      (libsource (lib "CherryMX_Footprints") (part "Cherry_Switch"))
    )
    (comp (ref "S78")
      (value "Cherry")
      (footprint "CHERRY-MX-LED-1U")
      (description "Cherry SPST Keyswitch")
      (libsource (lib "CherryMX_Footprints") (part "Cherry_Switch"))
    )
    (comp (ref "S79")
      (value "Cherry")
      (footprint "CHERRY-MX-LED-1U")
      (description "Cherry SPST Keyswitch")
      (libsource (lib "CherryMX_Footprints") (part "Cherry_Switch"))
    )
    (comp (ref "S80")
      (value "Cherry")
      (footprint "CHERRY-MX-LED-1U")
      (description "Cherry SPST Keyswitch")
      (libsource (lib "CherryMX_Footprints") (part "Cherry_Switch"))
    )
    (comp (ref "S81")
      (value "Cherry")
      (footprint "CHERRY-MX-LED-1U")
      (description "Cherry SPST Keyswitch")
      (libsource (lib "CherryMX_Footprints") (part "Cherry_Switch"))
    )
    (comp (ref "S82")
      (value "Cherry")
      (footprint "CHERRY-MX-LED-1U")
      (description "Cherry SPST Keyswitch")
      (libsource (lib "CherryMX_Footprints") (part "Cherry_Switch"))
    )
    (comp (ref "S83")
      (value "Cherry")
      (footprint "CHERRY-MX-LED-1U")
      (description "Cherry SPST Keyswitch")
      (libsource (lib "CherryMX_Footprints") (part "Cherry_Switch"))
    )
  )
  (nets
    (net (code "1") (name "Col0") (class "Default")
      (node (ref "S0") (pin "0") (pinfunction "0_0") (pintype "passive"))
      (node (ref "S1") (pin "0") (pinfunction "0_0") (pintype "passive"))
      (node (ref "S16") (pin "0") (pinfunction "0_0") (pintype "passive"))
      (node (ref "S17") (pin "0") (pinfunction "0_0") (pintype "passive"))
      (node (ref "S31") (pin "0") (pinfunction "0_0") (pintype "passive"))
      (node (ref "S32") (pin "0") (pinfunction "0_0") (pintype "passive"))
      (node (ref "S46") (pin "0") (pinfunction "0_0") (pintype "passive"))
      (node (ref "S47") (pin "0") (pinfunction "0_0") (pintype "passive"))
      (node (ref "S60") (pin "0") (pinfunction "0_0") (pintype "passive"))
      (node (ref "S74") (pin "0") (pinfunction "0_0") (pintype "passive"))
      (node (ref "S75") (pin "0") (pinfunction "0_0") (pintype "passive"))
    )
    (net (code "2") (name "Col1") (class "Default")
      (node (ref "S18") (pin "0") (pinfunction "0_0") (pintype "passive"))
      (node (ref "S19") (pin "0") (pinfunction "0_0") (pintype "passive"))
      (node (ref "S2") (pin "0") (pinfunction "0_0") (pintype "passive"))
      (node (ref "S3") (pin "0") (pinfunction "0_0") (pintype "passive"))
      (node (ref "S33") (pin "0") (pinfunction "0_0") (pintype "passive"))
      (node (ref "S34") (pin "0") (pinfunction "0_0") (pintype "passive"))
      (node (ref "S48") (pin "0") (pinfunction "0_0") (pintype "passive"))
      (node (ref "S49") (pin "0") (pinfunction "0_0") (pintype "passive"))
      (node (ref "S61") (pin "0") (pinfunction "0_0") (pintype "passive"))
      (node (ref "S62") (pin "0") (pinfunction "0_0") (pintype "passive"))
      (node (ref "S76") (pin "0") (pinfunction "0_0") (pintype "passive"))
    )
    (net (code "3") (name "Col2") (class "Default")
      (node (ref "S20") (pin "0") (pinfunction "0_0") (pintype "passive"))
      (node (ref "S21") (pin "0") (pinfunction "0_0") (pintype "passive"))
      (node (ref "S35") (pin "0") (pinfunction "0_0") (pintype "passive"))
      (node (ref "S36") (pin "0") (pinfunction "0_0") (pintype "passive"))
      (node (ref "S4") (pin "0") (pinfunction "0_0") (pintype "passive"))
      (node (ref "S5") (pin "0") (pinfunction "0_0") (pintype "passive"))
      (node (ref "S50") (pin "0") (pinfunction "0_0") (pintype "passive"))
      (node (ref "S51") (pin "0") (pinfunction "0_0") (pintype "passive"))
      (node (ref "S63") (pin "0") (pinfunction "0_0") (pintype "passive"))
      (node (ref "S64") (pin "0") (pinfunction "0_0") (pintype "passive"))
    )
    (net (code "4") (name "Col3") (class "Default")
      (node (ref "S22") (pin "0") (pinfunction "0_0") (pintype "passive"))
      (node (ref "S23") (pin "0") (pinfunction "0_0") (pintype "passive"))
      (node (ref "S37") (pin "0") (pinfunction "0_0") (pintype "passive"))
      (node (ref "S38") (pin "0") (pinfunction "0_0") (pintype "passive"))
      (node (ref "S52") (pin "0") (pinfunction "0_0") (pintype "passive"))
      (node (ref "S53") (pin "0") (pinfunction "0_0") (pintype "passive"))
      (node (ref "S6") (pin "0") (pinfunction "0_0") (pintype "passive"))
      (node (ref "S65") (pin "0") (pinfunction "0_0") (pintype "passive"))
      (node (ref "S66") (pin "0") (pinfunction "0_0") (pintype "passive"))
      (node (ref "S7") (pin "0") (pinfunction "0_0") (pintype "passive"))
      (node (ref "S77") (pin "0") (pinfunction "0_0") (pintype "passive"))
    )
    (net (code "5") (name "Col4") (class "Default")
      (node (ref "S24") (pin "0") (pinfunction "0_0") (pintype "passive"))
      (node (ref "S25") (pin "0") (pinfunction "0_0") (pintype "passive"))
      (node (ref "S39") (pin "0") (pinfunction "0_0") (pintype "passive"))
      (node (ref "S40") (pin "0") (pinfunction "0_0") (pintype "passive"))
      (node (ref "S54") (pin "0") (pinfunction "0_0") (pintype "passive"))
      (node (ref "S55") (pin "0") (pinfunction "0_0") (pintype "passive"))
      (node (ref "S67") (pin "0") (pinfunction "0_0") (pintype "passive"))
      (node (ref "S68") (pin "0") (pinfunction "0_0") (pintype "passive"))
      (node (ref "S8") (pin "0") (pinfunction "0_0") (pintype "passive"))
      (node (ref "S9") (pin "0") (pinfunction "0_0") (pintype "passive"))
    )
    (net (code "6") (name "Col5") (class "Default")
      (node (ref "S10") (pin "0") (pinfunction "0_0") (pintype "passive"))
      (node (ref "S11") (pin "0") (pinfunction "0_0") (pintype "passive"))
      (node (ref "S26") (pin "0") (pinfunction "0_0") (pintype "passive"))
      (node (ref "S27") (pin "0") (pinfunction "0_0") (pintype "passive"))
      (node (ref "S41") (pin "0") (pinfunction "0_0") (pintype "passive"))
      (node (ref "S42") (pin "0") (pinfunction "0_0") (pintype "passive"))
      (node (ref "S56") (pin "0") (pinfunction "0_0") (pintype "passive"))
      (node (ref "S57") (pin "0") (pinfunction "0_0") (pintype "passive"))
      (node (ref "S69") (pin "0") (pinfunction "0_0") (pintype "passive"))
      (node (ref "S70") (pin "0") (pinfunction "0_0") (pintype "passive"))
      (node (ref "S78") (pin "0") (pinfunction "0_0") (pintype "passive"))
      (node (ref "S79") (pin "0") (pinfunction "0_0") (pintype "passive"))
    )
    (net (code "7") (name "Col6") (class "Default")
      (node (ref "S12") (pin "0") (pinfunction "0_0") (pintype "passive"))
      (node (ref "S13") (pin "0") (pinfunction "0_0") (pintype "passive"))
      (node (ref "S28") (pin "0") (pinfunction "0_0") (pintype "passive"))
      (node (ref "S29") (pin "0") (pinfunction "0_0") (pintype "passive"))
      (node (ref "S43") (pin "0") (pinfunction "0_0") (pintype "passive"))
      (node (ref "S58") (pin "0") (pinfunction "0_0") (pintype "passive"))
      (node (ref "S71") (pin "0") (pinfunction "0_0") (pintype "passive"))
      (node (ref "S80") (pin "0") (pinfunction "0_0") (pintype "passive"))
      (node (ref "S81") (pin "0") (pinfunction "0_0") (pintype "passive"))
    )
    (net (code "8") (name "Col7") (class "Default")
      (node (ref "S14") (pin "0") (pinfunction "0_0") (pintype "passive"))
      (node (ref "S15") (pin "0") (pinfunction "0_0") (pintype "passive"))
      (node (ref "S30") (pin "0") (pinfunction "0_0") (pintype "passive"))
      (node (ref "S44") (pin "0") (pinfunction "0_0") (pintype "passive"))
      (node (ref "S45") (pin "0") (pinfunction "0_0") (pintype "passive"))
      (node (ref "S59") (pin "0") (pinfunction "0_0") (pintype "passive"))
      (node (ref "S72") (pin "0") (pinfunction "0_0") (pintype "passive"))
      (node (ref "S73") (pin "0") (pinfunction "0_0") (pintype "passive"))
      (node (ref "S82") (pin "0") (pinfunction "0_0") (pintype "passive"))
      (node (ref "S83") (pin "0") (pinfunction "0_0") (pintype "passive"))
    )
    (net (code "9") (name "Net-(D0-PadA)") (class "Default")
      (node (ref "D0") (pin "A") (pinfunction "A_A") (pintype "passive"))
      (node (ref "S0") (pin "1") (pinfunction "1_1") (pintype "passive"))
    )
    (net (code "10") (name "Net-(D1-PadA)") (class "Default")
      (node (ref "D1") (pin "A") (pinfunction "A_A") (pintype "passive"))
      (node (ref "S1") (pin "1") (pinfunction "1_1") (pintype "passive"))
    )
    (net (code "11") (name "Net-(D2-PadA)") (class "Default")
      (node (ref "D2") (pin "A") (pinfunction "A_A") (pintype "passive"))
      (node (ref "S2") (pin "1") (pinfunction "1_1") (pintype "passive"))
    )
    (net (code "12") (name "Net-(D3-PadA)") (class "Default")
      (node (ref "D3") (pin "A") (pinfunction "A_A") (pintype "passive"))
      (node (ref "S3") (pin "1") (pinfunction "1_1") (pintype "passive"))
    )
    (net (code "13") (name "Net-(D4-PadA)") (class "Default")
      (node (ref "D4") (pin "A") (pinfunction "A_A") (pintype "passive"))
      (node (ref "S4") (pin "1") (pinfunction "1_1") (pintype "passive"))
    )
    (net (code "14") (name "Net-(D5-PadA)") (class "Default")
      (node (ref "D5") (pin "A") (pinfunction "A_A") (pintype "passive"))
      (node (ref "S5") (pin "1") (pinfunction "1_1") (pintype "passive"))
    )
    (net (code "15") (name "Net-(D6-PadA)") (class "Default")
      (node (ref "D6") (pin "A") (pinfunction "A_A") (pintype "passive"))
      (node (ref "S6") (pin "1") (pinfunction "1_1") (pintype "passive"))
    )
    (net (code "16") (name "Net-(D7-PadA)") (class "Default")
      (node (ref "D7") (pin "A") (pinfunction "A_A") (pintype "passive"))
      (node (ref "S7") (pin "1") (pinfunction "1_1") (pintype "passive"))
    )
    (net (code "17") (name "Net-(D8-PadA)") (class "Default")
      (node (ref "D8") (pin "A") (pinfunction "A_A") (pintype "passive"))
      (node (ref "S8") (pin "1") (pinfunction "1_1") (pintype "passive"))
    )
    (net (code "18") (name "Net-(D9-PadA)") (class "Default")
      (node (ref "D9") (pin "A") (pinfunction "A_A") (pintype "passive"))
      (node (ref "S9") (pin "1") (pinfunction "1_1") (pintype "passive"))
    )
    (net (code "19") (name "Net-(D10-PadA)") (class "Default")
      (node (ref "D10") (pin "A") (pinfunction "A_A") (pintype "passive"))
      (node (ref "S10") (pin "1") (pinfunction "1_1") (pintype "passive"))
    )
    (net (code "20") (name "Net-(D11-PadA)") (class "Default")
      (node (ref "D11") (pin "A") (pinfunction "A_A") (pintype "passive"))
      (node (ref "S11") (pin "1") (pinfunction "1_1") (pintype "passive"))
    )
    (net (code "21") (name "Net-(D12-PadA)") (class "Default")
      (node (ref "D12") (pin "A") (pinfunction "A_A") (pintype "passive"))
      (node (ref "S12") (pin "1") (pinfunction "1_1") (pintype "passive"))
    )
    (net (code "22") (name "Net-(D13-PadA)") (class "Default")
      (node (ref "D13") (pin "A") (pinfunction "A_A") (pintype "passive"))
      (node (ref "S13") (pin "1") (pinfunction "1_1") (pintype "passive"))
    )
    (net (code "23") (name "Net-(D14-PadA)") (class "Default")
      (node (ref "D14") (pin "A") (pinfunction "A_A") (pintype "passive"))
      (node (ref "S14") (pin "1") (pinfunction "1_1") (pintype "passive"))
    )
    (net (code "24") (name "Net-(D15-PadA)") (class "Default")
      (node (ref "D15") (pin "A") (pinfunction "A_A") (pintype "passive"))
      (node (ref "S15") (pin "1") (pinfunction "1_1") (pintype "passive"))
    )
    (net (code "25") (name "Net-(D16-PadA)") (class "Default")
      (node (ref "D16") (pin "A") (pinfunction "A_A") (pintype "passive"))
      (node (ref "S16") (pin "1") (pinfunction "1_1") (pintype "passive"))
    )
    (net (code "26") (name "Net-(D17-PadA)") (class "Default")
      (node (ref "D17") (pin "A") (pinfunction "A_A") (pintype "passive"))
      (node (ref "S17") (pin "1") (pinfunction "1_1") (pintype "passive"))
    )
    (net (code "27") (name "Net-(D18-PadA)") (class "Default")
      (node (ref "D18") (pin "A") (pinfunction "A_A") (pintype "passive"))
      (node (ref "S18") (pin "1") (pinfunction "1_1") (pintype "passive"))
    )
    (net (code "28") (name "Net-(D19-PadA)") (class "Default")
      (node (ref "D19") (pin "A") (pinfunction "A_A") (pintype "passive"))
      (node (ref "S19") (pin "1") (pinfunction "1_1") (pintype "passive"))
    )
    (net (code "29") (name "Net-(D20-PadA)") (class "Default")
      (node (ref "D20") (pin "A") (pinfunction "A_A") (pintype "passive"))
      (node (ref "S20") (pin "1") (pinfunction "1_1") (pintype "passive"))
    )
    (net (code "30") (name "Net-(D21-PadA)") (class "Default")
      (node (ref "D21") (pin "A") (pinfunction "A_A") (pintype "passive"))
      (node (ref "S21") (pin "1") (pinfunction "1_1") (pintype "passive"))
    )
    (net (code "31") (name "Net-(D22-PadA)") (class "Default")
      (node (ref "D22") (pin "A") (pinfunction "A_A") (pintype "passive"))
      (node (ref "S22") (pin "1") (pinfunction "1_1") (pintype "passive"))
    )
    (net (code "32") (name "Net-(D23-PadA)") (class "Default")
      (node (ref "D23") (pin "A") (pinfunction "A_A") (pintype "passive"))
      (node (ref "S23") (pin "1") (pinfunction "1_1") (pintype "passive"))
    )
    (net (code "33") (name "Net-(D24-PadA)") (class "Default")
      (node (ref "D24") (pin "A") (pinfunction "A_A") (pintype "passive"))
      (node (ref "S24") (pin "1") (pinfunction "1_1") (pintype "passive"))
    )
    (net (code "34") (name "Net-(D25-PadA)") (class "Default")
      (node (ref "D25") (pin "A") (pinfunction "A_A") (pintype "passive"))
      (node (ref "S25") (pin "1") (pinfunction "1_1") (pintype "passive"))
    )
    (net (code "35") (name "Net-(D26-PadA)") (class "Default")
      (node (ref "D26") (pin "A") (pinfunction "A_A") (pintype "passive"))
      (node (ref "S26") (pin "1") (pinfunction "1_1") (pintype "passive"))
    )
    (net (code "36") (name "Net-(D27-PadA)") (class "Default")
      (node (ref "D27") (pin "A") (pinfunction "A_A") (pintype "passive"))
      (node (ref "S27") (pin "1") (pinfunction "1_1") (pintype "passive"))
    )
    (net (code "37") (name "Net-(D28-PadA)") (class "Default")
      (node (ref "D28") (pin "A") (pinfunction "A_A") (pintype "passive"))
      (node (ref "S28") (pin "1") (pinfunction "1_1") (pintype "passive"))
    )
    (net (code "38") (name "Net-(D29-PadA)") (class "Default")
      (node (ref "D29") (pin "A") (pinfunction "A_A") (pintype "passive"))
      (node (ref "S29") (pin "1") (pinfunction "1_1") (pintype "passive"))
    )
    (net (code "39") (name "Net-(D30-PadA)") (class "Default")
      (node (ref "D30") (pin "A") (pinfunction "A_A") (pintype "passive"))
      (node (ref "S30") (pin "1") (pinfunction "1_1") (pintype "passive"))
    )
    (net (code "40") (name "Net-(D31-PadA)") (class "Default")
      (node (ref "D31") (pin "A") (pinfunction "A_A") (pintype "passive"))
      (node (ref "S31") (pin "1") (pinfunction "1_1") (pintype "passive"))
    )
    (net (code "41") (name "Net-(D32-PadA)") (class "Default")
      (node (ref "D32") (pin "A") (pinfunction "A_A") (pintype "passive"))
      (node (ref "S32") (pin "1") (pinfunction "1_1") (pintype "passive"))
    )
    (net (code "42") (name "Net-(D33-PadA)") (class "Default")
      (node (ref "D33") (pin "A") (pinfunction "A_A") (pintype "passive"))
      (node (ref "S33") (pin "1") (pinfunction "1_1") (pintype "passive"))
    )
    (net (code "43") (name "Net-(D34-PadA)") (class "Default")
      (node (ref "D34") (pin "A") (pinfunction "A_A") (pintype "passive"))
      (node (ref "S34") (pin "1") (pinfunction "1_1") (pintype "passive"))
    )
    (net (code "44") (name "Net-(D35-PadA)") (class "Default")
      (node (ref "D35") (pin "A") (pinfunction "A_A") (pintype "passive"))
      (node (ref "S35") (pin "1") (pinfunction "1_1") (pintype "passive"))
    )
    (net (code "45") (name "Net-(D36-PadA)") (class "Default")
      (node (ref "D36") (pin "A") (pinfunction "A_A") (pintype "passive"))
      (node (ref "S36") (pin "1") (pinfunction "1_1") (pintype "passive"))
    )
    (net (code "46") (name "Net-(D37-PadA)") (class "Default")
      (node (ref "D37") (pin "A") (pinfunction "A_A") (pintype "passive"))
      (node (ref "S37") (pin "1") (pinfunction "1_1") (pintype "passive"))
    )
    (net (code "47") (name "Net-(D38-PadA)") (class "Default")
      (node (ref "D38") (pin "A") (pinfunction "A_A") (pintype "passive"))
      (node (ref "S38") (pin "1") (pinfunction "1_1") (pintype "passive"))
    )
    (net (code "48") (name "Net-(D39-PadA)") (class "Default")
      (node (ref "D39") (pin "A") (pinfunction "A_A") (pintype "passive"))
      (node (ref "S39") (pin "1") (pinfunction "1_1") (pintype "passive"))
    )
    (net (code "49") (name "Net-(D40-PadA)") (class "Default")
      (node (ref "D40") (pin "A") (pinfunction "A_A") (pintype "passive"))
      (node (ref "S40") (pin "1") (pinfunction "1_1") (pintype "passive"))
    )
    (net (code "50") (name "Net-(D41-PadA)") (class "Default")
      (node (ref "D41") (pin "A") (pinfunction "A_A") (pintype "passive"))
      (node (ref "S41") (pin "1") (pinfunction "1_1") (pintype "passive"))
    )
    (net (code "51") (name "Net-(D42-PadA)") (class "Default")
      (node (ref "D42") (pin "A") (pinfunction "A_A") (pintype "passive"))
      (node (ref "S42") (pin "1") (pinfunction "1_1") (pintype "passive"))
    )
    (net (code "52") (name "Net-(D43-PadA)") (class "Default")
      (node (ref "D43") (pin "A") (pinfunction "A_A") (pintype "passive"))
      (node (ref "S43") (pin "1") (pinfunction "1_1") (pintype "passive"))
    )
    (net (code "53") (name "Net-(D44-PadA)") (class "Default")
      (node (ref "D44") (pin "A") (pinfunction "A_A") (pintype "passive"))
      (node (ref "S44") (pin "1") (pinfunction "1_1") (pintype "passive"))
    )
    (net (code "54") (name "Net-(D45-PadA)") (class "Default")
      (node (ref "D45") (pin "A") (pinfunction "A_A") (pintype "passive"))
      (node (ref "S45") (pin "1") (pinfunction "1_1") (pintype "passive"))
    )
    (net (code "55") (name "Net-(D46-PadA)") (class "Default")
      (node (ref "D46") (pin "A") (pinfunction "A_A") (pintype "passive"))
      (node (ref "S46") (pin "1") (pinfunction "1_1") (pintype "passive"))
    )
    (net (code "56") (name "Net-(D47-PadA)") (class "Default")
      (node (ref "D47") (pin "A") (pinfunction "A_A") (pintype "passive"))
      (node (ref "S47") (pin "1") (pinfunction "1_1") (pintype "passive"))
    )
    (net (code "57") (name "Net-(D48-PadA)") (class "Default")
      (node (ref "D48") (pin "A") (pinfunction "A_A") (pintype "passive"))
      (node (ref "S48") (pin "1") (pinfunction "1_1") (pintype "passive"))
    )
    (net (code "58") (name "Net-(D49-PadA)") (class "Default")
      (node (ref "D49") (pin "A") (pinfunction "A_A") (pintype "passive"))
      (node (ref "S49") (pin "1") (pinfunction "1_1") (pintype "passive"))
    )
    (net (code "59") (name "Net-(D50-PadA)") (class "Default")
      (node (ref "D50") (pin "A") (pinfunction "A_A") (pintype "passive"))
      (node (ref "S50") (pin "1") (pinfunction "1_1") (pintype "passive"))
    )
    (net (code "60") (name "Net-(D51-PadA)") (class "Default")
      (node (ref "D51") (pin "A") (pinfunction "A_A") (pintype "passive"))
      (node (ref "S51") (pin "1") (pinfunction "1_1") (pintype "passive"))
    )
    (net (code "61") (name "Net-(D52-PadA)") (class "Default")
      (node (ref "D52") (pin "A") (pinfunction "A_A") (pintype "passive"))
      (node (ref "S52") (pin "1") (pinfunction "1_1") (pintype "passive"))
    )
    (net (code "62") (name "Net-(D53-PadA)") (class "Default")
      (node (ref "D53") (pin "A") (pinfunction "A_A") (pintype "passive"))
      (node (ref "S53") (pin "1") (pinfunction "1_1") (pintype "passive"))
    )
    (net (code "63") (name "Net-(D54-PadA)") (class "Default")
      (node (ref "D54") (pin "A") (pinfunction "A_A") (pintype "passive"))
      (node (ref "S54") (pin "1") (pinfunction "1_1") (pintype "passive"))
    )
    (net (code "64") (name "Net-(D55-PadA)") (class "Default")
      (node (ref "D55") (pin "A") (pinfunction "A_A") (pintype "passive"))
      (node (ref "S55") (pin "1") (pinfunction "1_1") (pintype "passive"))
    )
    (net (code "65") (name "Net-(D56-PadA)") (class "Default")
      (node (ref "D56") (pin "A") (pinfunction "A_A") (pintype "passive"))
      (node (ref "S56") (pin "1") (pinfunction "1_1") (pintype "passive"))
    )
    (net (code "66") (name "Net-(D57-PadA)") (class "Default")
      (node (ref "D57") (pin "A") (pinfunction "A_A") (pintype "passive"))
      (node (ref "S57") (pin "1") (pinfunction "1_1") (pintype "passive"))
    )
    (net (code "67") (name "Net-(D58-PadA)") (class "Default")
      (node (ref "D58") (pin "A") (pinfunction "A_A") (pintype "passive"))
      (node (ref "S58") (pin "1") (pinfunction "1_1") (pintype "passive"))
    )
    (net (code "68") (name "Net-(D59-PadA)") (class "Default")
      (node (ref "D59") (pin "A") (pinfunction "A_A") (pintype "passive"))
      (node (ref "S59") (pin "1") (pinfunction "1_1") (pintype "passive"))
    )
    (net (code "69") (name "Net-(D60-PadA)") (class "Default")
      (node (ref "D60") (pin "A") (pinfunction "A_A") (pintype "passive"))
      (node (ref "S60") (pin "1") (pinfunction "1_1") (pintype "passive"))
    )
    (net (code "70") (name "Net-(D61-PadA)") (class "Default")
      (node (ref "D61") (pin "A") (pinfunction "A_A") (pintype "passive"))
      (node (ref "S61") (pin "1") (pinfunction "1_1") (pintype "passive"))
    )
    (net (code "71") (name "Net-(D62-PadA)") (class "Default")
      (node (ref "D62") (pin "A") (pinfunction "A_A") (pintype "passive"))
      (node (ref "S62") (pin "1") (pinfunction "1_1") (pintype "passive"))
    )
    (net (code "72") (name "Net-(D63-PadA)") (class "Default")
      (node (ref "D63") (pin "A") (pinfunction "A_A") (pintype "passive"))
      (node (ref "S63") (pin "1") (pinfunction "1_1") (pintype "passive"))
    )
    (net (code "73") (name "Net-(D64-PadA)") (class "Default")
      (node (ref "D64") (pin "A") (pinfunction "A_A") (pintype "passive"))
      (node (ref "S64") (pin "1") (pinfunction "1_1") (pintype "passive"))
    )
    (net (code "74") (name "Net-(D65-PadA)") (class "Default")
      (node (ref "D65") (pin "A") (pinfunction "A_A") (pintype "passive"))
      (node (ref "S65") (pin "1") (pinfunction "1_1") (pintype "passive"))
    )
    (net (code "75") (name "Net-(D66-PadA)") (class "Default")
      (node (ref "D66") (pin "A") (pinfunction "A_A") (pintype "passive"))
      (node (ref "S66") (pin "1") (pinfunction "1_1") (pintype "passive"))
    )
    (net (code "76") (name "Net-(D67-PadA)") (class "Default")
      (node (ref "D67") (pin "A") (pinfunction "A_A") (pintype "passive"))
      (node (ref "S67") (pin "1") (pinfunction "1_1") (pintype "passive"))
    )
    (net (code "77") (name "Net-(D68-PadA)") (class "Default")
      (node (ref "D68") (pin "A") (pinfunction "A_A") (pintype "passive"))
      (node (ref "S68") (pin "1") (pinfunction "1_1") (pintype "passive"))
    )
    (net (code "78") (name "Net-(D69-PadA)") (class "Default")
      (node (ref "D69") (pin "A") (pinfunction "A_A") (pintype "passive"))
      (node (ref "S69") (pin "1") (pinfunction "1_1") (pintype "passive"))
    )
    (net (code "79") (name "Net-(D70-PadA)") (class "Default")
      (node (ref "D70") (pin "A") (pinfunction "A_A") (pintype "passive"))
      (node (ref "S70") (pin "1") (pinfunction "1_1") (pintype "passive"))
    )
    (net (code "80") (name "Net-(D71-PadA)") (class "Default")
      (node (ref "D71") (pin "A") (pinfunction "A_A") (pintype "passive"))
      (node (ref "S71") (pin "1") (pinfunction "1_1") (pintype "passive"))
    )
    (net (code "81") (name "Net-(D72-PadA)") (class "Default")
      (node (ref "D72") (pin "A") (pinfunction "A_A") (pintype "passive"))
      (node (ref "S72") (pin "1") (pinfunction "1_1") (pintype "passive"))
    )
    (net (code "82") (name "Net-(D73-PadA)") (class "Default")
      (node (ref "D73") (pin "A") (pinfunction "A_A") (pintype "passive"))
      (node (ref "S73") (pin "1") (pinfunction "1_1") (pintype "passive"))
    )
    (net (code "83") (name "Net-(D74-PadA)") (class "Default")
      (node (ref "D74") (pin "A") (pinfunction "A_A") (pintype "passive"))
      (node (ref "S74") (pin "1") (pinfunction "1_1") (pintype "passive"))
    )
    (net (code "84") (name "Net-(D75-PadA)") (class "Default")
      (node (ref "D75") (pin "A") (pinfunction "A_A") (pintype "passive"))
      (node (ref "S75") (pin "1") (pinfunction "1_1") (pintype "passive"))
    )
    (net (code "85") (name "Net-(D76-PadA)") (class "Default")
      (node (ref "D76") (pin "A") (pinfunction "A_A") (pintype "passive"))
      (node (ref "S76") (pin "1") (pinfunction "1_1") (pintype "passive"))
    )
    (net (code "86") (name "Net-(D77-PadA)") (class "Default")
      (node (ref "D77") (pin "A") (pinfunction "A_A") (pintype "passive"))
      (node (ref "S77") (pin "1") (pinfunction "1_1") (pintype "passive"))
    )
    (net (code "87") (name "Net-(D78-PadA)") (class "Default")
      (node (ref "D78") (pin "A") (pinfunction "A_A") (pintype "passive"))
      (node (ref "S78") (pin "1") (pinfunction "1_1") (pintype "passive"))
    )
    (net (code "88") (name "Net-(D79-PadA)") (class "Default")
      (node (ref "D79") (pin "A") (pinfunction "A_A") (pintype "passive"))
      (node (ref "S79") (pin "1") (pinfunction "1_1") (pintype "passive"))
    )
    (net (code "89") (name "Net-(D80-PadA)") (class "Default")
      (node (ref "D80") (pin "A") (pinfunction "A_A") (pintype "passive"))
      (node (ref "S80") (pin "1") (pinfunction "1_1") (pintype "passive"))
    )
    (net (code "90") (name "Net-(D81-PadA)") (class "Default")
      (node (ref "D81") (pin "A") (pinfunction "A_A") (pintype "passive"))
      (node (ref "S81") (pin "1") (pinfunction "1_1") (pintype "passive"))
    )
    (net (code "91") (name "Net-(D82-PadA)") (class "Default")
      (node (ref "D82") (pin "A") (pinfunction "A_A") (pintype "passive"))
      (node (ref "S82") (pin "1") (pinfunction "1_1") (pintype "passive"))
    )
    (net (code "92") (name "Net-(D83-PadA)") (class "Default")
      (node (ref "D83") (pin "A") (pinfunction "A_A") (pintype "passive"))
      (node (ref "S83") (pin "1") (pinfunction "1_1") (pintype "passive"))
    )
    (net (code "93") (name "Row0") (class "Default")
      (node (ref "D0") (pin "C") (pinfunction "C_C") (pintype "passive"))
      (node (ref "D10") (pin "C") (pinfunction "C_C") (pintype "passive"))
      (node (ref "D12") (pin "C") (pinfunction "C_C") (pintype "passive"))
      (node (ref "D14") (pin "C") (pinfunction "C_C") (pintype "passive"))
      (node (ref "D2") (pin "C") (pinfunction "C_C") (pintype "passive"))
      (node (ref "D4") (pin "C") (pinfunction "C_C") (pintype "passive"))
      (node (ref "D6") (pin "C") (pinfunction "C_C") (pintype "passive"))
      (node (ref "D8") (pin "C") (pinfunction "C_C") (pintype "passive"))
    )
    (net (code "94") (name "Row1") (class "Default")
      (node (ref "D1") (pin "C") (pinfunction "C_C") (pintype "passive"))
      (node (ref "D11") (pin "C") (pinfunction "C_C") (pintype "passive"))
      (node (ref "D13") (pin "C") (pinfunction "C_C") (pintype "passive"))
      (node (ref "D15") (pin "C") (pinfunction "C_C") (pintype "passive"))
      (node (ref "D3") (pin "C") (pinfunction "C_C") (pintype "passive"))
      (node (ref "D5") (pin "C") (pinfunction "C_C") (pintype "passive"))
      (node (ref "D7") (pin "C") (pinfunction "C_C") (pintype "passive"))
      (node (ref "D9") (pin "C") (pinfunction "C_C") (pintype "passive"))
    )
    (net (code "95") (name "Row2") (class "Default")
      (node (ref "D16") (pin "C") (pinfunction "C_C") (pintype "passive"))
      (node (ref "D18") (pin "C") (pinfunction "C_C") (pintype "passive"))
      (node (ref "D20") (pin "C") (pinfunction "C_C") (pintype "passive"))
      (node (ref "D22") (pin "C") (pinfunction "C_C") (pintype "passive"))
      (node (ref "D24") (pin "C") (pinfunction "C_C") (pintype "passive"))
      (node (ref "D26") (pin "C") (pinfunction "C_C") (pintype "passive"))
      (node (ref "D28") (pin "C") (pinfunction "C_C") (pintype "passive"))
    )
    (net (code "96") (name "Row3") (class "Default")
      (node (ref "D17") (pin "C") (pinfunction "C_C") (pintype "passive"))
      (node (ref "D19") (pin "C") (pinfunction "C_C") (pintype "passive"))
      (node (ref "D21") (pin "C") (pinfunction "C_C") (pintype "passive"))
      (node (ref "D23") (pin "C") (pinfunction "C_C") (pintype "passive"))
      (node (ref "D25") (pin "C") (pinfunction "C_C") (pintype "passive"))
      (node (ref "D27") (pin "C") (pinfunction "C_C") (pintype "passive"))
      (node (ref "D29") (pin "C") (pinfunction "C_C") (pintype "passive"))
      (node (ref "D30") (pin "C") (pinfunction "C_C") (pintype "passive"))
    )
    (net (code "97") (name "Row4") (class "Default")
      (node (ref "D31") (pin "C") (pinfunction "C_C") (pintype "passive"))
      (node (ref "D33") (pin "C") (pinfunction "C_C") (pintype "passive"))
      (node (ref "D35") (pin "C") (pinfunction "C_C") (pintype "passive"))
      (node (ref "D37") (pin "C") (pinfunction "C_C") (pintype "passive"))
      (node (ref "D39") (pin "C") (pinfunction "C_C") (pintype "passive"))
      (node (ref "D41") (pin "C") (pinfunction "C_C") (pintype "passive"))
      (node (ref "D43") (pin "C") (pinfunction "C_C") (pintype "passive"))
      (node (ref "D44") (pin "C") (pinfunction "C_C") (pintype "passive"))
    )
    (net (code "98") (name "Row5") (class "Default")
      (node (ref "D32") (pin "C") (pinfunction "C_C") (pintype "passive"))
      (node (ref "D34") (pin "C") (pinfunction "C_C") (pintype "passive"))
      (node (ref "D36") (pin "C") (pinfunction "C_C") (pintype "passive"))
      (node (ref "D38") (pin "C") (pinfunction "C_C") (pintype "passive"))
      (node (ref "D40") (pin "C") (pinfunction "C_C") (pintype "passive"))
      (node (ref "D42") (pin "C") (pinfunction "C_C") (pintype "passive"))
      (node (ref "D45") (pin "C") (pinfunction "C_C") (pintype "passive"))
    )
    (net (code "99") (name "Row6") (class "Default")
      (node (ref "D46") (pin "C") (pinfunction "C_C") (pintype "passive"))
      (node (ref "D48") (pin "C") (pinfunction "C_C") (pintype "passive"))
      (node (ref "D50") (pin "C") (pinfunction "C_C") (pintype "passive"))
      (node (ref "D52") (pin "C") (pinfunction "C_C") (pintype "passive"))
      (node (ref "D54") (pin "C") (pinfunction "C_C") (pintype "passive"))
      (node (ref "D56") (pin "C") (pinfunction "C_C") (pintype "passive"))
    )
    (net (code "100") (name "Row7") (class "Default")
      (node (ref "D47") (pin "C") (pinfunction "C_C") (pintype "passive"))
      (node (ref "D49") (pin "C") (pinfunction "C_C") (pintype "passive"))
      (node (ref "D51") (pin "C") (pinfunction "C_C") (pintype "passive"))
      (node (ref "D53") (pin "C") (pinfunction "C_C") (pintype "passive"))
      (node (ref "D55") (pin "C") (pinfunction "C_C") (pintype "passive"))
      (node (ref "D57") (pin "C") (pinfunction "C_C") (pintype "passive"))
      (node (ref "D58") (pin "C") (pinfunction "C_C") (pintype "passive"))
      (node (ref "D59") (pin "C") (pinfunction "C_C") (pintype "passive"))
    )
    (net (code "101") (name "Row8") (class "Default")
      (node (ref "D60") (pin "C") (pinfunction "C_C") (pintype "passive"))
      (node (ref "D61") (pin "C") (pinfunction "C_C") (pintype "passive"))
      (node (ref "D63") (pin "C") (pinfunction "C_C") (pintype "passive"))
      (node (ref "D65") (pin "C") (pinfunction "C_C") (pintype "passive"))
      (node (ref "D67") (pin "C") (pinfunction "C_C") (pintype "passive"))
      (node (ref "D69") (pin "C") (pinfunction "C_C") (pintype "passive"))
      (node (ref "D71") (pin "C") (pinfunction "C_C") (pintype "passive"))
      (node (ref "D72") (pin "C") (pinfunction "C_C") (pintype "passive"))
    )
    (net (code "102") (name "Row9") (class "Default")
      (node (ref "D62") (pin "C") (pinfunction "C_C") (pintype "passive"))
      (node (ref "D64") (pin "C") (pinfunction "C_C") (pintype "passive"))
      (node (ref "D66") (pin "C") (pinfunction "C_C") (pintype "passive"))
      (node (ref "D68") (pin "C") (pinfunction "C_C") (pintype "passive"))
      (node (ref "D70") (pin "C") (pinfunction "C_C") (pintype "passive"))
      (node (ref "D73") (pin "C") (pinfunction "C_C") (pintype "passive"))
    )
    (net (code "103") (name "Row10") (class "Default")
      (node (ref "D74") (pin "C") (pinfunction "C_C") (pintype "passive"))
      (node (ref "D76") (pin "C") (pinfunction "C_C") (pintype "passive"))
      (node (ref "D77") (pin "C") (pinfunction "C_C") (pintype "passive"))
      (node (ref "D78") (pin "C") (pinfunction "C_C") (pintype "passive"))
      (node (ref "D80") (pin "C") (pinfunction "C_C") (pintype "passive"))
      (node (ref "D82") (pin "C") (pinfunction "C_C") (pintype "passive"))
    )
    (net (code "104") (name "Row11") (class "Default")
      (node (ref "D75") (pin "C") (pinfunction "C_C") (pintype "passive"))
      (node (ref "D79") (pin "C") (pinfunction "C_C") (pintype "passive"))
      (node (ref "D81") (pin "C") (pinfunction "C_C") (pintype "passive"))
      (node (ref "D83") (pin "C") (pinfunction "C_C") (pintype "passive"))
    )
  )
)
